# radio_module_V1_0.net
KiCad netlist of a schematic drawn in EAGLE
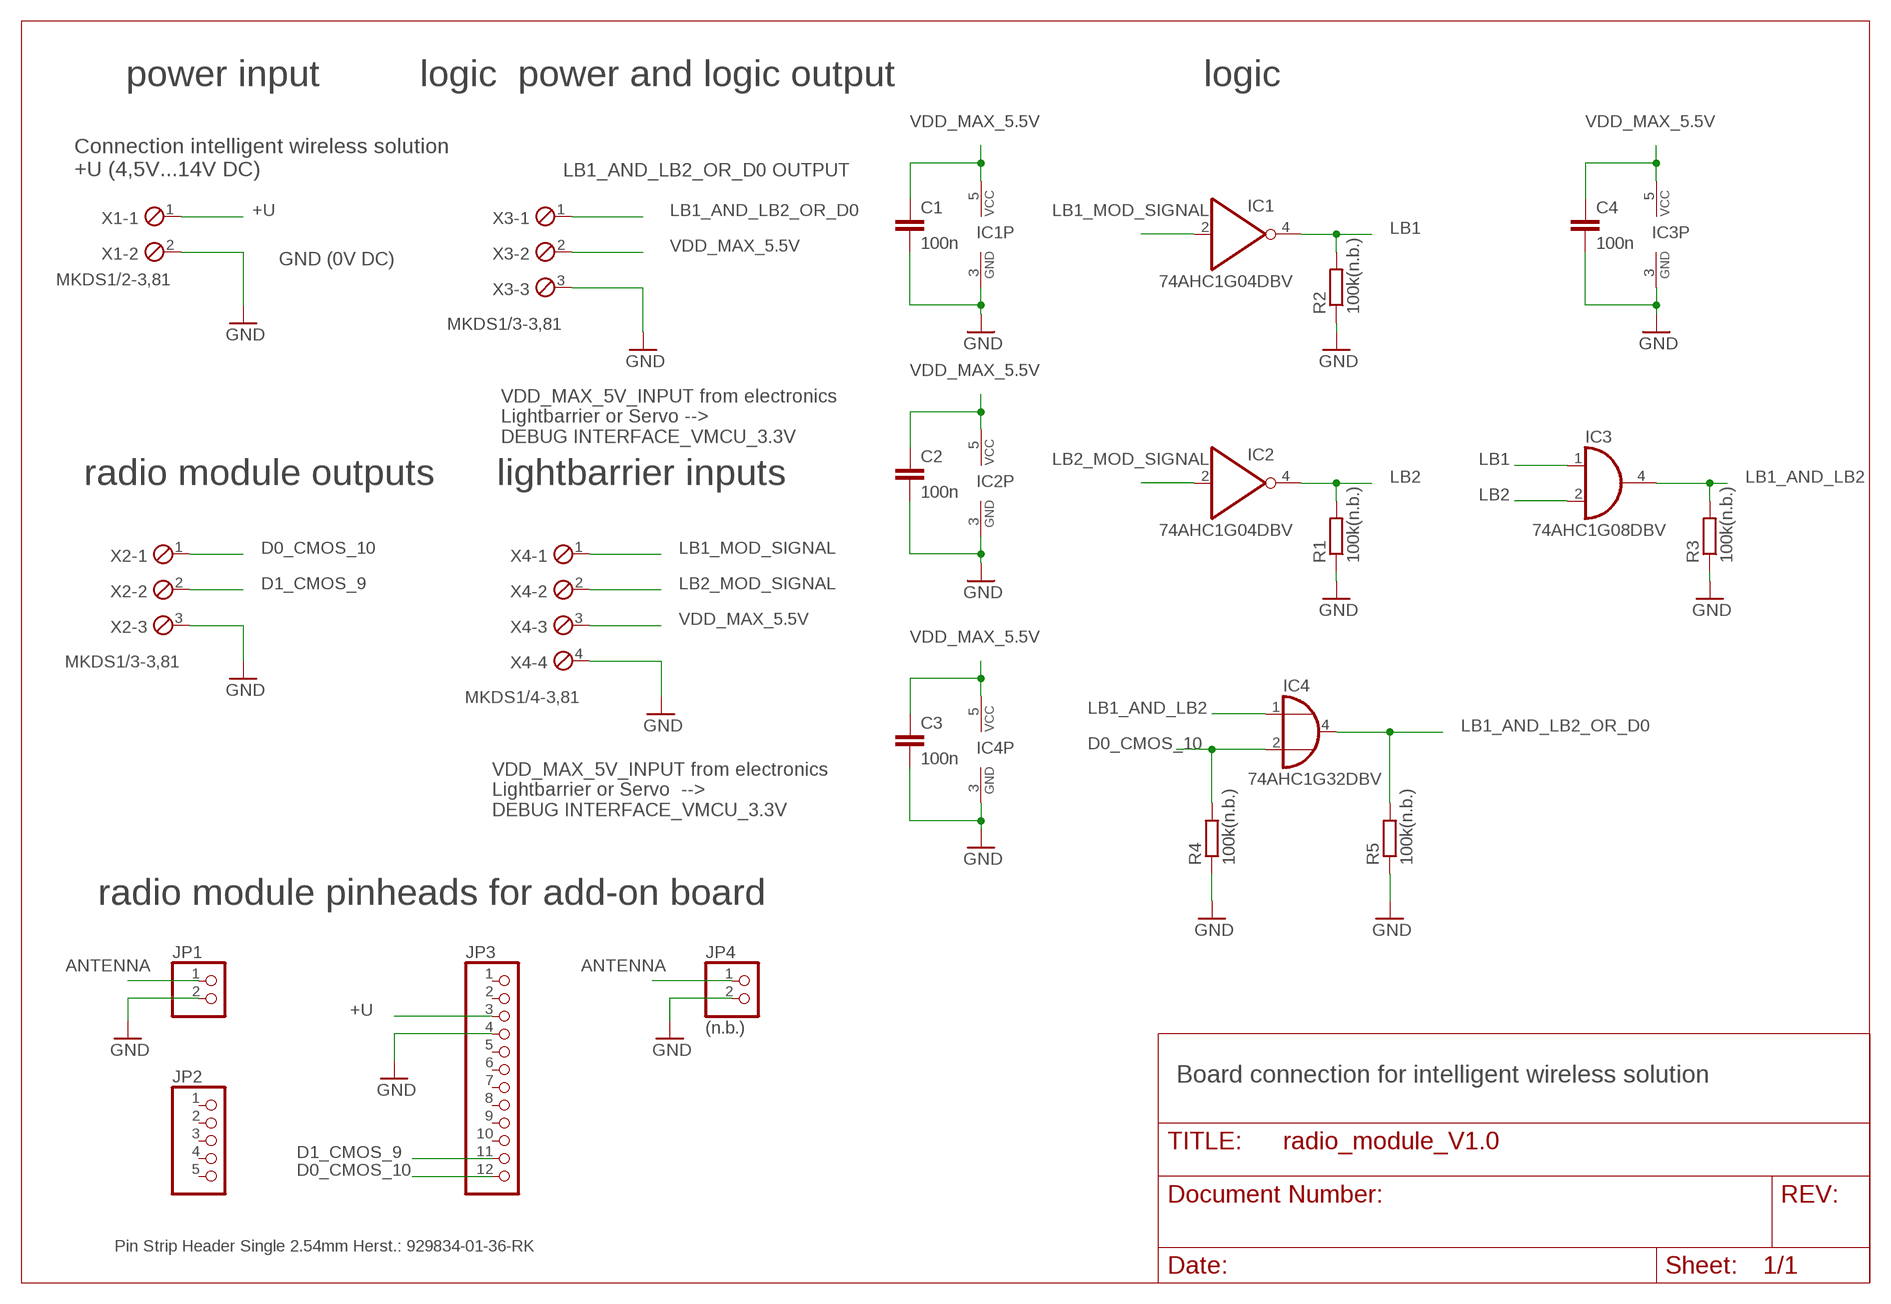
[diagram p0: schematic, sheet 1]

(export (version "E")
  (design (tool "Eeschema 10.0.6"))
  (components
    (comp (ref "C1")
      (value "100n")
      (footprint "eagle-import:C0805")
      (libsource (lib "eagle-import") (part "C-EUC0805"))
    )
    (comp (ref "C2")
      (value "100n")
      (footprint "eagle-import:C0805")
      (libsource (lib "eagle-import") (part "C-EUC0805"))
    )
    (comp (ref "C3")
      (value "100n")
      (footprint "eagle-import:C0805")
      (libsource (lib "eagle-import") (part "C-EUC0805"))
    )
    (comp (ref "C4")
      (value "100n")
      (footprint "eagle-import:C0805")
      (libsource (lib "eagle-import") (part "C-EUC0805"))
    )
    (comp (ref "IC1")
      (value "74AHC1G04DBV")
      (footprint "eagle-import:SOT23-5")
      (libsource (lib "eagle-import") (part "741G04DBVAHC"))
    )
    (comp (ref "IC2")
      (value "74AHC1G04DBV")
      (footprint "eagle-import:SOT23-5")
      (libsource (lib "eagle-import") (part "741G04DBVAHC"))
    )
    (comp (ref "IC3")
      (value "74AHC1G08DBV")
      (footprint "eagle-import:SOT23-5")
      (libsource (lib "eagle-import") (part "741G08DBVAHC"))
    )
    (comp (ref "IC4")
      (value "74AHC1G32DBV")
      (footprint "eagle-import:SOT23-5")
      (libsource (lib "eagle-import") (part "741G32DBVAHC"))
    )
    (comp (ref "JP1")
      (value "PINHD-1X2")
      (footprint "eagle-import:1X02")
      (libsource (lib "eagle-import") (part "PINHD-1X2"))
    )
    (comp (ref "JP2")
      (value "PINHD-1X5")
      (footprint "eagle-import:1X05")
      (libsource (lib "eagle-import") (part "PINHD-1X5"))
    )
    (comp (ref "JP3")
      (value "PINHD-1X12")
      (footprint "eagle-import:1X12")
      (libsource (lib "eagle-import") (part "PINHD-1X12"))
    )
    (comp (ref "JP4")
      (value "(n.b.)")
      (footprint "eagle-import:1X02")
      (libsource (lib "eagle-import") (part "PINHD-1X2"))
    )
    (comp (ref "R1")
      (value "100k(n.b.)")
      (footprint "eagle-import:R0805")
      (libsource (lib "eagle-import") (part "R-EU_R0805"))
    )
    (comp (ref "R2")
      (value "100k(n.b.)")
      (footprint "eagle-import:R0805")
      (libsource (lib "eagle-import") (part "R-EU_R0805"))
    )
    (comp (ref "R3")
      (value "100k(n.b.)")
      (footprint "eagle-import:R0805")
      (libsource (lib "eagle-import") (part "R-EU_R0805"))
    )
    (comp (ref "R4")
      (value "100k(n.b.)")
      (footprint "eagle-import:R0805")
      (libsource (lib "eagle-import") (part "R-EU_R0805"))
    )
    (comp (ref "R5")
      (value "100k(n.b.)")
      (footprint "eagle-import:R0805")
      (libsource (lib "eagle-import") (part "R-EU_R0805"))
    )
    (comp (ref "X1")
      (value "MKDS1/2-3,81")
      (footprint "eagle-import:2POL381")
      (libsource (lib "eagle-import") (part "MKDS1/2-3,81"))
    )
    (comp (ref "X2")
      (value "MKDS1/3-3,81")
      (footprint "eagle-import:3POL381")
      (libsource (lib "eagle-import") (part "MKDS1/3-3,81"))
    )
    (comp (ref "X3")
      (value "MKDS1/3-3,81")
      (footprint "eagle-import:3POL381")
      (libsource (lib "eagle-import") (part "MKDS1/3-3,81"))
    )
    (comp (ref "X4")
      (value "MKDS1/4-3,81")
      (footprint "eagle-import:4POL381")
      (libsource (lib "eagle-import") (part "MKDS1/4-3,81"))
    )
  )
  (nets
    (net (code "1") (name "/+U") (class "Default")
      (node (ref "JP3") (pin "3") (pinfunction "3_3") (pintype "passive"))
      (node (ref "X1") (pin "1") (pinfunction "1_1") (pintype "passive"))
    )
    (net (code "2") (name "/ANTENNA") (class "Default")
      (node (ref "JP1") (pin "1") (pinfunction "1_1") (pintype "passive"))
      (node (ref "JP4") (pin "1") (pinfunction "1_1") (pintype "passive"))
    )
    (net (code "3") (name "/D0_CMOS_10") (class "Default")
      (node (ref "IC4") (pin "2") (pinfunction "I1_2") (pintype "input"))
      (node (ref "JP3") (pin "12") (pinfunction "12_12") (pintype "passive"))
      (node (ref "R4") (pin "2") (pinfunction "2_2") (pintype "passive"))
      (node (ref "X2") (pin "1") (pinfunction "1_1") (pintype "passive"))
    )
    (net (code "4") (name "/D1_CMOS_9") (class "Default")
      (node (ref "JP3") (pin "11") (pinfunction "11_11") (pintype "passive"))
      (node (ref "X2") (pin "2") (pinfunction "1_2") (pintype "passive"))
    )
    (net (code "5") (name "/LB1") (class "Default")
      (node (ref "IC1") (pin "4") (pinfunction "O_4") (pintype "output"))
      (node (ref "IC3") (pin "1") (pinfunction "I0_1") (pintype "input"))
      (node (ref "R2") (pin "2") (pinfunction "2_2") (pintype "passive"))
    )
    (net (code "6") (name "/LB1_AND_LB2") (class "Default")
      (node (ref "IC3") (pin "4") (pinfunction "O_4") (pintype "output"))
      (node (ref "IC4") (pin "1") (pinfunction "I0_1") (pintype "input"))
      (node (ref "R3") (pin "2") (pinfunction "2_2") (pintype "passive"))
    )
    (net (code "7") (name "/LB1_AND_LB2_OR_D0") (class "Default")
      (node (ref "IC4") (pin "4") (pinfunction "O_4") (pintype "output"))
      (node (ref "R5") (pin "2") (pinfunction "2_2") (pintype "passive"))
      (node (ref "X3") (pin "1") (pinfunction "1_1") (pintype "passive"))
    )
    (net (code "8") (name "/LB1_MOD_SIGNAL") (class "Default")
      (node (ref "IC1") (pin "2") (pinfunction "I_2") (pintype "input"))
      (node (ref "X4") (pin "1") (pinfunction "1_1") (pintype "passive"))
    )
    (net (code "9") (name "/LB2") (class "Default")
      (node (ref "IC2") (pin "4") (pinfunction "O_4") (pintype "output"))
      (node (ref "IC3") (pin "2") (pinfunction "I1_2") (pintype "input"))
      (node (ref "R1") (pin "2") (pinfunction "2_2") (pintype "passive"))
    )
    (net (code "10") (name "/LB2_MOD_SIGNAL") (class "Default")
      (node (ref "IC2") (pin "2") (pinfunction "I_2") (pintype "input"))
      (node (ref "X4") (pin "2") (pinfunction "1_2") (pintype "passive"))
    )
    (net (code "11") (name "/VDD_MAX_5.5V") (class "Default")
      (node (ref "C1") (pin "1") (pinfunction "1_1") (pintype "passive"))
      (node (ref "C2") (pin "1") (pinfunction "1_1") (pintype "passive"))
      (node (ref "C3") (pin "1") (pinfunction "1_1") (pintype "passive"))
      (node (ref "C4") (pin "1") (pinfunction "1_1") (pintype "passive"))
      (node (ref "IC1") (pin "5") (pinfunction "VCC_5") (pintype "power_in"))
      (node (ref "IC2") (pin "5") (pinfunction "VCC_5") (pintype "power_in"))
      (node (ref "IC3") (pin "5") (pinfunction "VCC_5") (pintype "power_in"))
      (node (ref "IC4") (pin "5") (pinfunction "VCC_5") (pintype "power_in"))
      (node (ref "X3") (pin "2") (pinfunction "1_2") (pintype "passive"))
      (node (ref "X4") (pin "3") (pinfunction "1_3") (pintype "passive"))
    )
    (net (code "12") (name "GND") (class "Default")
      (node (ref "C1") (pin "2") (pinfunction "2_2") (pintype "passive"))
      (node (ref "C2") (pin "2") (pinfunction "2_2") (pintype "passive"))
      (node (ref "C3") (pin "2") (pinfunction "2_2") (pintype "passive"))
      (node (ref "C4") (pin "2") (pinfunction "2_2") (pintype "passive"))
      (node (ref "IC1") (pin "3") (pinfunction "GND_3") (pintype "power_in"))
      (node (ref "IC2") (pin "3") (pinfunction "GND_3") (pintype "power_in"))
      (node (ref "IC3") (pin "3") (pinfunction "GND_3") (pintype "power_in"))
      (node (ref "IC4") (pin "3") (pinfunction "GND_3") (pintype "power_in"))
      (node (ref "JP1") (pin "2") (pinfunction "2_2") (pintype "passive"))
      (node (ref "JP3") (pin "4") (pinfunction "4_4") (pintype "passive"))
      (node (ref "JP4") (pin "2") (pinfunction "2_2") (pintype "passive"))
      (node (ref "R1") (pin "1") (pinfunction "1_1") (pintype "passive"))
      (node (ref "R2") (pin "1") (pinfunction "1_1") (pintype "passive"))
      (node (ref "R3") (pin "1") (pinfunction "1_1") (pintype "passive"))
      (node (ref "R4") (pin "1") (pinfunction "1_1") (pintype "passive"))
      (node (ref "R5") (pin "1") (pinfunction "1_1") (pintype "passive"))
      (node (ref "X1") (pin "2") (pinfunction "1_2") (pintype "passive"))
      (node (ref "X2") (pin "3") (pinfunction "1_3") (pintype "passive"))
      (node (ref "X3") (pin "3") (pinfunction "1_3") (pintype "passive"))
      (node (ref "X4") (pin "4") (pinfunction "1_4") (pintype "passive"))
    )
    (net (code "13") (name "unconnected-(JP2-Pad1)") (class "Default")
      (node (ref "JP2") (pin "1") (pinfunction "1_1") (pintype "passive"))
    )
    (net (code "14") (name "unconnected-(JP2-Pad2)") (class "Default")
      (node (ref "JP2") (pin "2") (pinfunction "2_2") (pintype "passive"))
    )
    (net (code "15") (name "unconnected-(JP2-Pad3)") (class "Default")
      (node (ref "JP2") (pin "3") (pinfunction "3_3") (pintype "passive"))
    )
    (net (code "16") (name "unconnected-(JP2-Pad4)") (class "Default")
      (node (ref "JP2") (pin "4") (pinfunction "4_4") (pintype "passive"))
    )
    (net (code "17") (name "unconnected-(JP2-Pad5)") (class "Default")
      (node (ref "JP2") (pin "5") (pinfunction "5_5") (pintype "passive"))
    )
    (net (code "18") (name "unconnected-(JP3-Pad1)") (class "Default")
      (node (ref "JP3") (pin "1") (pinfunction "1_1") (pintype "passive"))
    )
    (net (code "19") (name "unconnected-(JP3-Pad2)") (class "Default")
      (node (ref "JP3") (pin "2") (pinfunction "2_2") (pintype "passive"))
    )
    (net (code "20") (name "unconnected-(JP3-Pad5)") (class "Default")
      (node (ref "JP3") (pin "5") (pinfunction "5_5") (pintype "passive"))
    )
    (net (code "21") (name "unconnected-(JP3-Pad6)") (class "Default")
      (node (ref "JP3") (pin "6") (pinfunction "6_6") (pintype "passive"))
    )
    (net (code "22") (name "unconnected-(JP3-Pad7)") (class "Default")
      (node (ref "JP3") (pin "7") (pinfunction "7_7") (pintype "passive"))
    )
    (net (code "23") (name "unconnected-(JP3-Pad8)") (class "Default")
      (node (ref "JP3") (pin "8") (pinfunction "8_8") (pintype "passive"))
    )
    (net (code "24") (name "unconnected-(JP3-Pad9)") (class "Default")
      (node (ref "JP3") (pin "9") (pinfunction "9_9") (pintype "passive"))
    )
    (net (code "25") (name "unconnected-(JP3-Pad10)") (class "Default")
      (node (ref "JP3") (pin "10") (pinfunction "10_10") (pintype "passive"))
    )
  )
)
